# DMGC-PWR-01_2-0.net
KiCad netlist of a schematic drawn in EAGLE
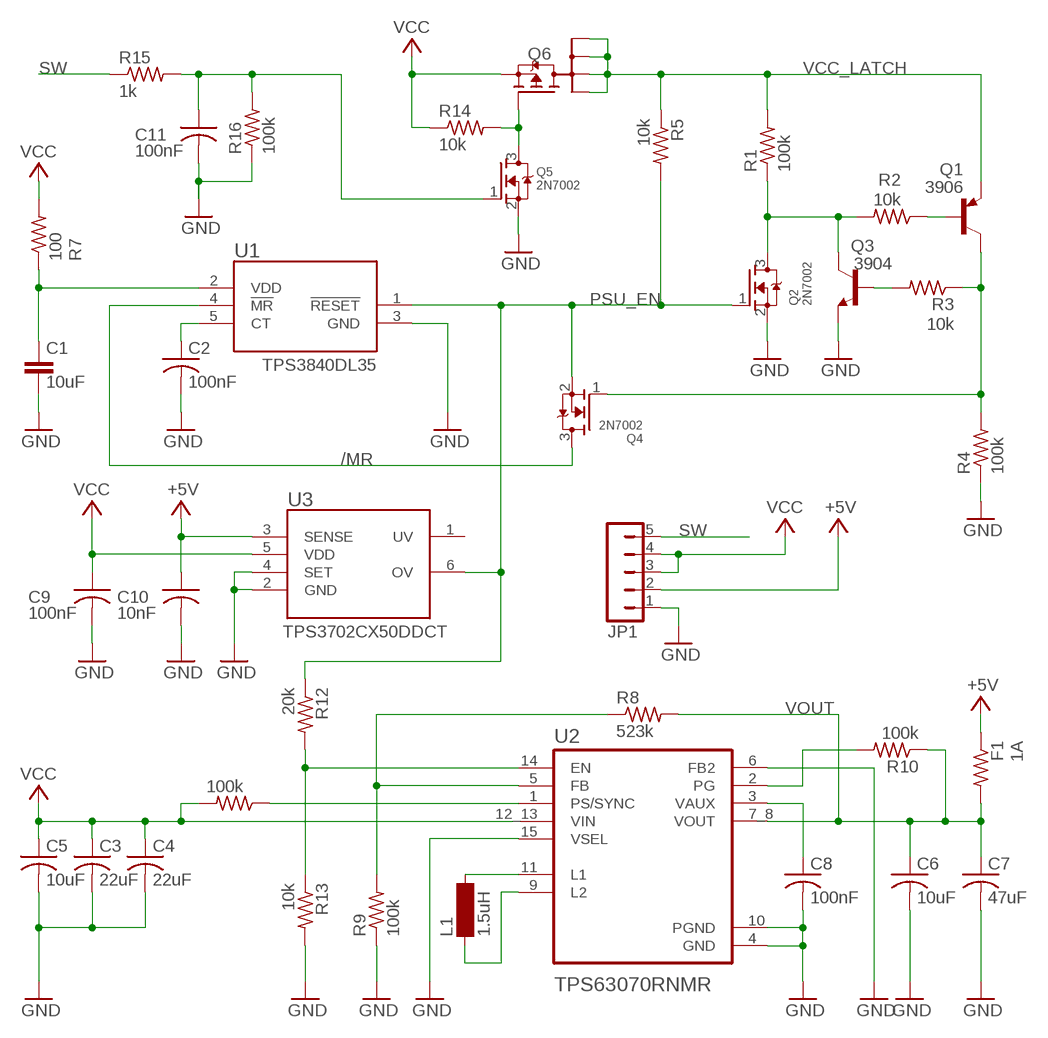
[diagram p0: schematic, sheet 1]

(export (version "E")
  (design (tool "Eeschema 10.0.6"))
  (components
    (comp (ref "C1")
      (value "10uF")
      (footprint "eagle-import:C0603")
      (libsource (lib "eagle-import") (part "C-EUC0603"))
    )
    (comp (ref "C2")
      (value "100nF")
      (footprint "eagle-import:C0603")
      (libsource (lib "eagle-import") (part "C-USC0603"))
    )
    (comp (ref "C3")
      (value "22uF")
      (footprint "eagle-import:C1206")
      (libsource (lib "eagle-import") (part "C-USC1206"))
    )
    (comp (ref "C4")
      (value "22uF")
      (footprint "eagle-import:C1206")
      (libsource (lib "eagle-import") (part "C-USC1206"))
    )
    (comp (ref "C5")
      (value "10uF")
      (footprint "eagle-import:C0603")
      (libsource (lib "eagle-import") (part "C-USC0603"))
    )
    (comp (ref "C6")
      (value "10uF")
      (footprint "eagle-import:C0603")
      (libsource (lib "eagle-import") (part "C-USC0603"))
    )
    (comp (ref "C7")
      (value "47uF")
      (footprint "eagle-import:C1206")
      (libsource (lib "eagle-import") (part "C-USC1206"))
    )
    (comp (ref "C8")
      (value "100nF")
      (footprint "eagle-import:C0603")
      (libsource (lib "eagle-import") (part "C-USC0603"))
    )
    (comp (ref "C9")
      (value "100nF")
      (footprint "eagle-import:C0603")
      (libsource (lib "eagle-import") (part "C-USC0603"))
    )
    (comp (ref "C10")
      (value "10nF")
      (footprint "eagle-import:C0603")
      (libsource (lib "eagle-import") (part "C-USC0603"))
    )
    (comp (ref "C11")
      (value "100nF")
      (footprint "eagle-import:C0603")
      (libsource (lib "eagle-import") (part "C-USC0603"))
    )
    (comp (ref "F1")
      (value "1A")
      (footprint "eagle-import:R0603")
      (libsource (lib "eagle-import") (part "R-US_R0603"))
    )
    (comp (ref "JP1")
      (value "JP5")
      (footprint "eagle-import:JP5")
      (libsource (lib "eagle-import") (part "JP5"))
    )
    (comp (ref "L1")
      (value "1.5uH")
      (footprint "eagle-import:1212")
      (libsource (lib "eagle-import") (part "LQH3NPN2R2"))
    )
    (comp (ref "Q1")
      (value "MMBT3906LT1SMD")
      (footprint "eagle-import:SOT23-BEC")
      (libsource (lib "eagle-import") (part "MMBT3906SMDLT1"))
    )
    (comp (ref "Q2")
      (value "2N7002")
      (footprint "eagle-import:SOT23")
      (libsource (lib "eagle-import") (part "MOSFET-NREFLOW"))
    )
    (comp (ref "Q3")
      (value "3904")
      (footprint "eagle-import:SOT23-BEC")
      (libsource (lib "eagle-import") (part "-NPN-SOT23-BECMMBT3904LT1"))
    )
    (comp (ref "Q4")
      (value "2N7002")
      (footprint "eagle-import:SOT23")
      (libsource (lib "eagle-import") (part "MOSFET-NREFLOW"))
    )
    (comp (ref "Q5")
      (value "2N7002")
      (footprint "eagle-import:SOT23")
      (libsource (lib "eagle-import") (part "MOSFET-NREFLOW"))
    )
    (comp (ref "Q6")
      (value "SI1401EDH")
      (footprint "eagle-import:SOT363_INFINEON")
      (libsource (lib "eagle-import") (part "SI1401EDH"))
    )
    (comp (ref "R1")
      (value "100k")
      (footprint "eagle-import:R0603")
      (libsource (lib "eagle-import") (part "R-US_R0603"))
    )
    (comp (ref "R2")
      (value "10k")
      (footprint "eagle-import:R0603")
      (libsource (lib "eagle-import") (part "R-US_R0603"))
    )
    (comp (ref "R3")
      (value "10k")
      (footprint "eagle-import:R0603")
      (libsource (lib "eagle-import") (part "R-US_R0603"))
    )
    (comp (ref "R4")
      (value "100k")
      (footprint "eagle-import:R0603")
      (libsource (lib "eagle-import") (part "R-US_R0603"))
    )
    (comp (ref "R5")
      (value "10k")
      (footprint "eagle-import:R0603")
      (libsource (lib "eagle-import") (part "R-US_R0603"))
    )
    (comp (ref "R7")
      (value "100")
      (footprint "eagle-import:R0603")
      (libsource (lib "eagle-import") (part "R-US_R0603"))
    )
    (comp (ref "R8")
      (value "523k")
      (footprint "eagle-import:R0603")
      (libsource (lib "eagle-import") (part "R-US_R0603"))
    )
    (comp (ref "R9")
      (value "100k")
      (footprint "eagle-import:R0603")
      (libsource (lib "eagle-import") (part "R-US_R0603"))
    )
    (comp (ref "R10")
      (value "100k")
      (footprint "eagle-import:R0603")
      (libsource (lib "eagle-import") (part "R-US_R0603"))
    )
    (comp (ref "R11")
      (value "100k")
      (footprint "eagle-import:R0603")
      (libsource (lib "eagle-import") (part "R-US_R0603"))
    )
    (comp (ref "R12")
      (value "20k")
      (footprint "eagle-import:R0603")
      (libsource (lib "eagle-import") (part "R-US_R0603"))
    )
    (comp (ref "R13")
      (value "10k")
      (footprint "eagle-import:R0603")
      (libsource (lib "eagle-import") (part "R-US_R0603"))
    )
    (comp (ref "R14")
      (value "10k")
      (footprint "eagle-import:R0603")
      (libsource (lib "eagle-import") (part "R-US_R0603"))
    )
    (comp (ref "R15")
      (value "1k")
      (footprint "eagle-import:R0603")
      (libsource (lib "eagle-import") (part "R-US_R0603"))
    )
    (comp (ref "R16")
      (value "100k")
      (footprint "eagle-import:R0603")
      (libsource (lib "eagle-import") (part "R-US_R0603"))
    )
    (comp (ref "U1")
      (value "TPS3840")
      (footprint "eagle-import:SOT-23-5")
      (libsource (lib "eagle-import") (part "TPS3840"))
    )
    (comp (ref "U2")
      (value "TPS63070RNMR")
      (footprint "eagle-import:VREG_TPS63070RNMR")
      (fields (field (name "MF") "Texas Instruments"))
      (libsource (lib "eagle-import") (part "TPS63070RNMR"))
    )
    (comp (ref "U3")
      (value "TPS3702")
      (footprint "eagle-import:SOT-23-6")
      (libsource (lib "eagle-import") (part "TPS3702"))
    )
  )
  (nets
    (net (code "1") (name "+5V") (class "Default")
      (node (ref "C10") (pin "1") (pinfunction "1_1") (pintype "passive"))
      (node (ref "F1") (pin "1") (pinfunction "1_1") (pintype "passive"))
      (node (ref "JP1") (pin "2") (pinfunction "2_2") (pintype "passive"))
      (node (ref "U3") (pin "3") (pinfunction "SENSE_3") (pintype "input"))
    )
    (net (code "2") (name "/PSU_EN") (class "Default")
      (node (ref "Q2") (pin "1") (pinfunction "G_1") (pintype "bidirectional"))
      (node (ref "Q4") (pin "2") (pinfunction "S_2") (pintype "bidirectional"))
      (node (ref "R12") (pin "1") (pinfunction "1_1") (pintype "passive"))
      (node (ref "R5") (pin "2") (pinfunction "2_2") (pintype "passive"))
      (node (ref "U1") (pin "1") (pinfunction "~{RESET}_1") (pintype "output"))
      (node (ref "U3") (pin "6") (pinfunction "OV_6") (pintype "output"))
    )
    (net (code "3") (name "/SW") (class "Default")
      (node (ref "JP1") (pin "5") (pinfunction "5_5") (pintype "passive"))
      (node (ref "R15") (pin "1") (pinfunction "1_1") (pintype "passive"))
    )
    (net (code "4") (name "/VCC_LATCH") (class "Default")
      (node (ref "Q1") (pin "E") (pinfunction "E_E") (pintype "passive"))
      (node (ref "Q6") (pin "1") (pinfunction "D1_1") (pintype "passive"))
      (node (ref "Q6") (pin "2") (pinfunction "D2_2") (pintype "passive"))
      (node (ref "Q6") (pin "5") (pinfunction "D5_5") (pintype "passive"))
      (node (ref "Q6") (pin "6") (pinfunction "D6_6") (pintype "passive"))
      (node (ref "R1") (pin "2") (pinfunction "2_2") (pintype "passive"))
      (node (ref "R5") (pin "1") (pinfunction "1_1") (pintype "passive"))
    )
    (net (code "5") (name "/VOUT") (class "Default")
      (node (ref "C6") (pin "1") (pinfunction "1_1") (pintype "passive"))
      (node (ref "C7") (pin "1") (pinfunction "1_1") (pintype "passive"))
      (node (ref "F1") (pin "2") (pinfunction "2_2") (pintype "passive"))
      (node (ref "R10") (pin "1") (pinfunction "1_1") (pintype "passive"))
      (node (ref "R8") (pin "2") (pinfunction "2_2") (pintype "passive"))
      (node (ref "U2") (pin "7_8") (pinfunction "VOUT_7_8") (pintype "output"))
    )
    (net (code "6") (name "/{slash}MR") (class "Default")
      (node (ref "Q4") (pin "3") (pinfunction "D_3") (pintype "bidirectional"))
      (node (ref "U1") (pin "4") (pinfunction "~{MR}_4") (pintype "input"))
    )
    (net (code "7") (name "GND") (class "Default")
      (node (ref "C1") (pin "2") (pinfunction "2_2") (pintype "passive"))
      (node (ref "C10") (pin "2") (pinfunction "2_2") (pintype "passive"))
      (node (ref "C11") (pin "2") (pinfunction "2_2") (pintype "passive"))
      (node (ref "C2") (pin "2") (pinfunction "2_2") (pintype "passive"))
      (node (ref "C3") (pin "2") (pinfunction "2_2") (pintype "passive"))
      (node (ref "C4") (pin "2") (pinfunction "2_2") (pintype "passive"))
      (node (ref "C5") (pin "2") (pinfunction "2_2") (pintype "passive"))
      (node (ref "C6") (pin "2") (pinfunction "2_2") (pintype "passive"))
      (node (ref "C7") (pin "2") (pinfunction "2_2") (pintype "passive"))
      (node (ref "C8") (pin "2") (pinfunction "2_2") (pintype "passive"))
      (node (ref "C9") (pin "2") (pinfunction "2_2") (pintype "passive"))
      (node (ref "JP1") (pin "1") (pinfunction "1_1") (pintype "passive"))
      (node (ref "Q2") (pin "2") (pinfunction "S_2") (pintype "bidirectional"))
      (node (ref "Q3") (pin "E") (pinfunction "E_E") (pintype "passive"))
      (node (ref "Q5") (pin "2") (pinfunction "S_2") (pintype "bidirectional"))
      (node (ref "R13") (pin "2") (pinfunction "2_2") (pintype "passive"))
      (node (ref "R16") (pin "1") (pinfunction "1_1") (pintype "passive"))
      (node (ref "R4") (pin "1") (pinfunction "1_1") (pintype "passive"))
      (node (ref "R9") (pin "1") (pinfunction "1_1") (pintype "passive"))
      (node (ref "U1") (pin "3") (pinfunction "GND_3") (pintype "power_in"))
      (node (ref "U2") (pin "10") (pinfunction "PGND_10") (pintype "power_in"))
      (node (ref "U2") (pin "15") (pinfunction "VSEL_15") (pintype "input"))
      (node (ref "U2") (pin "4") (pinfunction "GND_4") (pintype "power_in"))
      (node (ref "U2") (pin "6") (pinfunction "FB2_6") (pintype "output"))
      (node (ref "U3") (pin "2") (pinfunction "GND_2") (pintype "power_in"))
      (node (ref "U3") (pin "4") (pinfunction "SET_4") (pintype "input"))
    )
    (net (code "8") (name "Net-(Q1-PadB)") (class "Default")
      (node (ref "Q1") (pin "B") (pinfunction "B_B") (pintype "passive"))
      (node (ref "R2") (pin "1") (pinfunction "1_1") (pintype "passive"))
    )
    (net (code "9") (name "Net-(Q2-D)") (class "Default")
      (node (ref "Q2") (pin "3") (pinfunction "D_3") (pintype "bidirectional"))
      (node (ref "Q3") (pin "C") (pinfunction "C_C") (pintype "passive"))
      (node (ref "R1") (pin "1") (pinfunction "1_1") (pintype "passive"))
      (node (ref "R2") (pin "2") (pinfunction "2_2") (pintype "passive"))
    )
    (net (code "10") (name "Net-(Q3-PadB)") (class "Default")
      (node (ref "Q3") (pin "B") (pinfunction "B_B") (pintype "passive"))
      (node (ref "R3") (pin "2") (pinfunction "2_2") (pintype "passive"))
    )
    (net (code "11") (name "Net-(Q4-G)") (class "Default")
      (node (ref "Q1") (pin "C") (pinfunction "C_C") (pintype "passive"))
      (node (ref "Q4") (pin "1") (pinfunction "G_1") (pintype "bidirectional"))
      (node (ref "R3") (pin "1") (pinfunction "1_1") (pintype "passive"))
      (node (ref "R4") (pin "2") (pinfunction "2_2") (pintype "passive"))
    )
    (net (code "12") (name "Net-(Q5-D)") (class "Default")
      (node (ref "Q5") (pin "3") (pinfunction "D_3") (pintype "bidirectional"))
      (node (ref "Q6") (pin "3") (pinfunction "G_3") (pintype "passive"))
      (node (ref "R14") (pin "2") (pinfunction "2_2") (pintype "passive"))
    )
    (net (code "13") (name "Net-(Q5-G)") (class "Default")
      (node (ref "C11") (pin "1") (pinfunction "1_1") (pintype "passive"))
      (node (ref "Q5") (pin "1") (pinfunction "G_1") (pintype "bidirectional"))
      (node (ref "R15") (pin "2") (pinfunction "2_2") (pintype "passive"))
      (node (ref "R16") (pin "2") (pinfunction "2_2") (pintype "passive"))
    )
    (net (code "14") (name "Net-(U1-CT)") (class "Default")
      (node (ref "C2") (pin "1") (pinfunction "1_1") (pintype "passive"))
      (node (ref "U1") (pin "5") (pinfunction "CT_5") (pintype "bidirectional"))
    )
    (net (code "15") (name "Net-(U1-VDD)") (class "Default")
      (node (ref "C1") (pin "1") (pinfunction "1_1") (pintype "passive"))
      (node (ref "R7") (pin "1") (pinfunction "1_1") (pintype "passive"))
      (node (ref "U1") (pin "2") (pinfunction "VDD_2") (pintype "power_in"))
    )
    (net (code "16") (name "Net-(U2-EN)") (class "Default")
      (node (ref "R12") (pin "2") (pinfunction "2_2") (pintype "passive"))
      (node (ref "R13") (pin "1") (pinfunction "1_1") (pintype "passive"))
      (node (ref "U2") (pin "14") (pinfunction "EN_14") (pintype "input"))
    )
    (net (code "17") (name "Net-(U2-FB)") (class "Default")
      (node (ref "R8") (pin "1") (pinfunction "1_1") (pintype "passive"))
      (node (ref "R9") (pin "2") (pinfunction "2_2") (pintype "passive"))
      (node (ref "U2") (pin "5") (pinfunction "FB_5") (pintype "input"))
    )
    (net (code "18") (name "Net-(U2-L1)") (class "Default")
      (node (ref "L1") (pin "2") (pinfunction "2_2") (pintype "passive"))
      (node (ref "U2") (pin "11") (pinfunction "L1_11") (pintype "bidirectional"))
    )
    (net (code "19") (name "Net-(U2-L2)") (class "Default")
      (node (ref "L1") (pin "1") (pinfunction "1_1") (pintype "passive"))
      (node (ref "U2") (pin "9") (pinfunction "L2_9") (pintype "bidirectional"))
    )
    (net (code "20") (name "Net-(U2-PG)") (class "Default")
      (node (ref "R10") (pin "2") (pinfunction "2_2") (pintype "passive"))
      (node (ref "U2") (pin "2") (pinfunction "PG_2") (pintype "output"))
    )
    (net (code "21") (name "Net-(U2-PS{slash}SYNC)") (class "Default")
      (node (ref "R11") (pin "1") (pinfunction "1_1") (pintype "passive"))
      (node (ref "U2") (pin "1") (pinfunction "PS/SYNC_1") (pintype "input"))
    )
    (net (code "22") (name "Net-(U2-VAUX)") (class "Default")
      (node (ref "C8") (pin "1") (pinfunction "1_1") (pintype "passive"))
      (node (ref "U2") (pin "3") (pinfunction "VAUX_3") (pintype "output"))
    )
    (net (code "23") (name "VCC") (class "Default")
      (node (ref "C3") (pin "1") (pinfunction "1_1") (pintype "passive"))
      (node (ref "C4") (pin "1") (pinfunction "1_1") (pintype "passive"))
      (node (ref "C5") (pin "1") (pinfunction "1_1") (pintype "passive"))
      (node (ref "C9") (pin "1") (pinfunction "1_1") (pintype "passive"))
      (node (ref "JP1") (pin "3") (pinfunction "3_3") (pintype "passive"))
      (node (ref "JP1") (pin "4") (pinfunction "4_4") (pintype "passive"))
      (node (ref "Q6") (pin "4") (pinfunction "S_4") (pintype "passive"))
      (node (ref "R11") (pin "2") (pinfunction "2_2") (pintype "passive"))
      (node (ref "R14") (pin "1") (pinfunction "1_1") (pintype "passive"))
      (node (ref "R7") (pin "2") (pinfunction "2_2") (pintype "passive"))
      (node (ref "U2") (pin "12_13") (pinfunction "VIN_12_13") (pintype "input"))
      (node (ref "U3") (pin "5") (pinfunction "VDD_5") (pintype "power_in"))
    )
    (net (code "24") (name "unconnected-(U3-UV-Pad1)") (class "Default")
      (node (ref "U3") (pin "1") (pinfunction "UV_1") (pintype "output"))
    )
  )
)
